# board.net
KiCad netlist of a schematic drawn in EAGLE
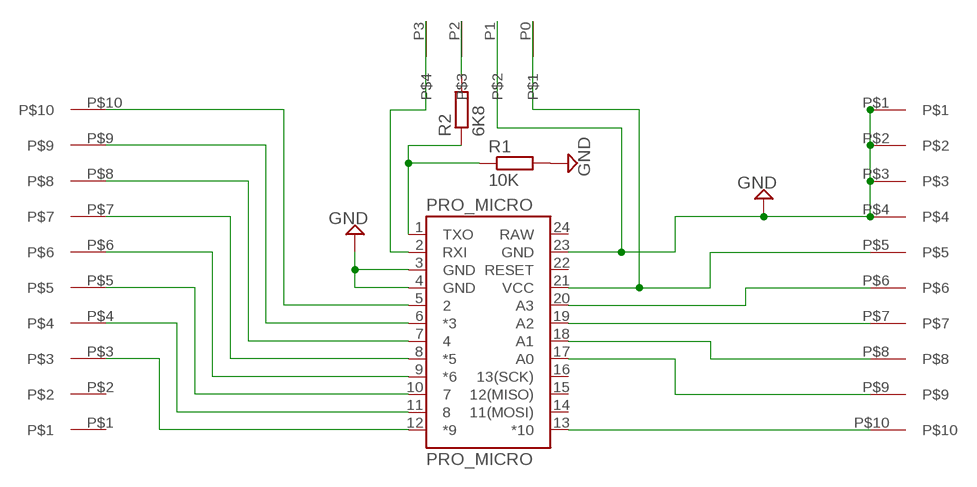
[diagram p0: schematic, sheet 1]

(export (version "E")
  (design (tool "Eeschema 10.0.6"))
  (components
    (comp (ref "PRO_MICRO")
      (value "PRO_MICRO")
      (footprint "eagle-import:SPARKFUN_PRO_MICRO")
      (libsource (lib "eagle-import") (part "SPARKFUN_PRO_MICRO"))
    )
    (comp (ref "R1")
      (value "10K")
      (footprint "eagle-import:R0805")
      (libsource (lib "eagle-import") (part "R-EU_R0805"))
    )
    (comp (ref "R2")
      (value "6K8")
      (footprint "eagle-import:R0805")
      (libsource (lib "eagle-import") (part "R-EU_R0805"))
    )
    (comp (ref "U$1")
      (value "TERMINAL10")
      (footprint "eagle-import:TERMINAL10")
      (libsource (lib "eagle-import") (part "TERMINAL10"))
    )
    (comp (ref "U$2")
      (value "TERMINAL10")
      (footprint "eagle-import:TERMINAL10")
      (libsource (lib "eagle-import") (part "TERMINAL10"))
    )
    (comp (ref "U$3")
      (value "TERMINAL4")
      (footprint "eagle-import:TERMINAL4")
      (libsource (lib "eagle-import") (part "TERMINAL4"))
    )
  )
  (nets
    (net (code "1") (name "/RAW") (class "Default")
      (node (ref "PRO_MICRO") (pin "24") (pinfunction "RAW_24") (pintype "power_in"))
    )
    (net (code "2") (name "GND") (class "Default")
      (node (ref "PRO_MICRO") (pin "23") (pinfunction "GND_23") (pintype "power_in"))
      (node (ref "PRO_MICRO") (pin "3") (pinfunction "GND_3") (pintype "power_in"))
      (node (ref "PRO_MICRO") (pin "4") (pinfunction "GND_4") (pintype "power_in"))
      (node (ref "R1") (pin "2") (pinfunction "2_2") (pintype "passive"))
      (node (ref "U$2") (pin "P$1") (pinfunction "P$1_P$1") (pintype "bidirectional"))
      (node (ref "U$2") (pin "P$2") (pinfunction "P$2_P$2") (pintype "bidirectional"))
      (node (ref "U$2") (pin "P$3") (pinfunction "P$3_P$3") (pintype "bidirectional"))
      (node (ref "U$2") (pin "P$4") (pinfunction "P$4_P$4") (pintype "bidirectional"))
      (node (ref "U$3") (pin "P1") (pinfunction "P$2_P1") (pintype "bidirectional"))
    )
    (net (code "3") (name "Net-(PRO_MICRO-*3)") (class "Default")
      (node (ref "PRO_MICRO") (pin "6") (pinfunction "*3_6") (pintype "bidirectional"))
      (node (ref "U$1") (pin "P$9") (pinfunction "P$9_P$9") (pintype "bidirectional"))
    )
    (net (code "4") (name "Net-(PRO_MICRO-*5)") (class "Default")
      (node (ref "PRO_MICRO") (pin "8") (pinfunction "*5_8") (pintype "bidirectional"))
      (node (ref "U$1") (pin "P$7") (pinfunction "P$7_P$7") (pintype "bidirectional"))
    )
    (net (code "5") (name "Net-(PRO_MICRO-*6)") (class "Default")
      (node (ref "PRO_MICRO") (pin "9") (pinfunction "*6_9") (pintype "bidirectional"))
      (node (ref "U$1") (pin "P$6") (pinfunction "P$6_P$6") (pintype "bidirectional"))
    )
    (net (code "6") (name "Net-(PRO_MICRO-*9)") (class "Default")
      (node (ref "PRO_MICRO") (pin "12") (pinfunction "*9_12") (pintype "bidirectional"))
      (node (ref "U$1") (pin "P$3") (pinfunction "P$3_P$3") (pintype "bidirectional"))
    )
    (net (code "7") (name "Net-(PRO_MICRO-*10)") (class "Default")
      (node (ref "PRO_MICRO") (pin "13") (pinfunction "*10_13") (pintype "bidirectional"))
      (node (ref "U$2") (pin "P$10") (pinfunction "P$10_P$10") (pintype "bidirectional"))
    )
    (net (code "8") (name "Net-(PRO_MICRO-2)") (class "Default")
      (node (ref "PRO_MICRO") (pin "5") (pinfunction "2_5") (pintype "bidirectional"))
      (node (ref "U$1") (pin "P$10") (pinfunction "P$10_P$10") (pintype "bidirectional"))
    )
    (net (code "9") (name "Net-(PRO_MICRO-4)") (class "Default")
      (node (ref "PRO_MICRO") (pin "7") (pinfunction "4_7") (pintype "bidirectional"))
      (node (ref "U$1") (pin "P$8") (pinfunction "P$8_P$8") (pintype "bidirectional"))
    )
    (net (code "10") (name "Net-(PRO_MICRO-7)") (class "Default")
      (node (ref "PRO_MICRO") (pin "10") (pinfunction "7_10") (pintype "bidirectional"))
      (node (ref "U$1") (pin "P$5") (pinfunction "P$5_P$5") (pintype "bidirectional"))
    )
    (net (code "11") (name "Net-(PRO_MICRO-8)") (class "Default")
      (node (ref "PRO_MICRO") (pin "11") (pinfunction "8_11") (pintype "bidirectional"))
      (node (ref "U$1") (pin "P$4") (pinfunction "P$4_P$4") (pintype "bidirectional"))
    )
    (net (code "12") (name "Net-(PRO_MICRO-A0)") (class "Default")
      (node (ref "PRO_MICRO") (pin "17") (pinfunction "A0_17") (pintype "bidirectional"))
      (node (ref "U$2") (pin "P$9") (pinfunction "P$9_P$9") (pintype "bidirectional"))
    )
    (net (code "13") (name "Net-(PRO_MICRO-A1)") (class "Default")
      (node (ref "PRO_MICRO") (pin "18") (pinfunction "A1_18") (pintype "bidirectional"))
      (node (ref "U$2") (pin "P$8") (pinfunction "P$8_P$8") (pintype "bidirectional"))
    )
    (net (code "14") (name "Net-(PRO_MICRO-A2)") (class "Default")
      (node (ref "PRO_MICRO") (pin "19") (pinfunction "A2_19") (pintype "bidirectional"))
      (node (ref "U$2") (pin "P$7") (pinfunction "P$7_P$7") (pintype "bidirectional"))
    )
    (net (code "15") (name "Net-(PRO_MICRO-A3)") (class "Default")
      (node (ref "PRO_MICRO") (pin "20") (pinfunction "A3_20") (pintype "bidirectional"))
      (node (ref "U$2") (pin "P$6") (pinfunction "P$6_P$6") (pintype "bidirectional"))
    )
    (net (code "16") (name "Net-(PRO_MICRO-RXI)") (class "Default")
      (node (ref "PRO_MICRO") (pin "2") (pinfunction "RXI_2") (pintype "bidirectional"))
      (node (ref "U$3") (pin "P3") (pinfunction "P$4_P3") (pintype "bidirectional"))
    )
    (net (code "17") (name "Net-(PRO_MICRO-TXO)") (class "Default")
      (node (ref "PRO_MICRO") (pin "1") (pinfunction "TXO_1") (pintype "bidirectional"))
      (node (ref "R1") (pin "1") (pinfunction "1_1") (pintype "passive"))
      (node (ref "R2") (pin "1") (pinfunction "1_1") (pintype "passive"))
    )
    (net (code "18") (name "Net-(PRO_MICRO-VCC)") (class "Default")
      (node (ref "PRO_MICRO") (pin "21") (pinfunction "VCC_21") (pintype "power_in"))
      (node (ref "U$2") (pin "P$5") (pinfunction "P$5_P$5") (pintype "bidirectional"))
      (node (ref "U$3") (pin "P0") (pinfunction "P$1_P0") (pintype "bidirectional"))
    )
    (net (code "19") (name "Net-(U$3-P$3)") (class "Default")
      (node (ref "R2") (pin "2") (pinfunction "2_2") (pintype "passive"))
      (node (ref "U$3") (pin "P2") (pinfunction "P$3_P2") (pintype "bidirectional"))
    )
    (net (code "20") (name "unconnected-(PRO_MICRO-11(MOSI)-Pad14)") (class "Default")
      (node (ref "PRO_MICRO") (pin "14") (pinfunction "11(MOSI)_14") (pintype "bidirectional"))
    )
    (net (code "21") (name "unconnected-(PRO_MICRO-12(MISO)-Pad15)") (class "Default")
      (node (ref "PRO_MICRO") (pin "15") (pinfunction "12(MISO)_15") (pintype "bidirectional"))
    )
    (net (code "22") (name "unconnected-(PRO_MICRO-13(SCK)-Pad16)") (class "Default")
      (node (ref "PRO_MICRO") (pin "16") (pinfunction "13(SCK)_16") (pintype "bidirectional"))
    )
    (net (code "23") (name "unconnected-(PRO_MICRO-RESET-Pad22)") (class "Default")
      (node (ref "PRO_MICRO") (pin "22") (pinfunction "RESET_22") (pintype "bidirectional"))
    )
    (net (code "24") (name "unconnected-(U$1-PadP$1)") (class "Default")
      (node (ref "U$1") (pin "P$1") (pinfunction "P$1_P$1") (pintype "bidirectional"))
    )
    (net (code "25") (name "unconnected-(U$1-PadP$2)") (class "Default")
      (node (ref "U$1") (pin "P$2") (pinfunction "P$2_P$2") (pintype "bidirectional"))
    )
  )
)
